# 128x64_ada.net
KiCad netlist of a schematic drawn in EAGLE
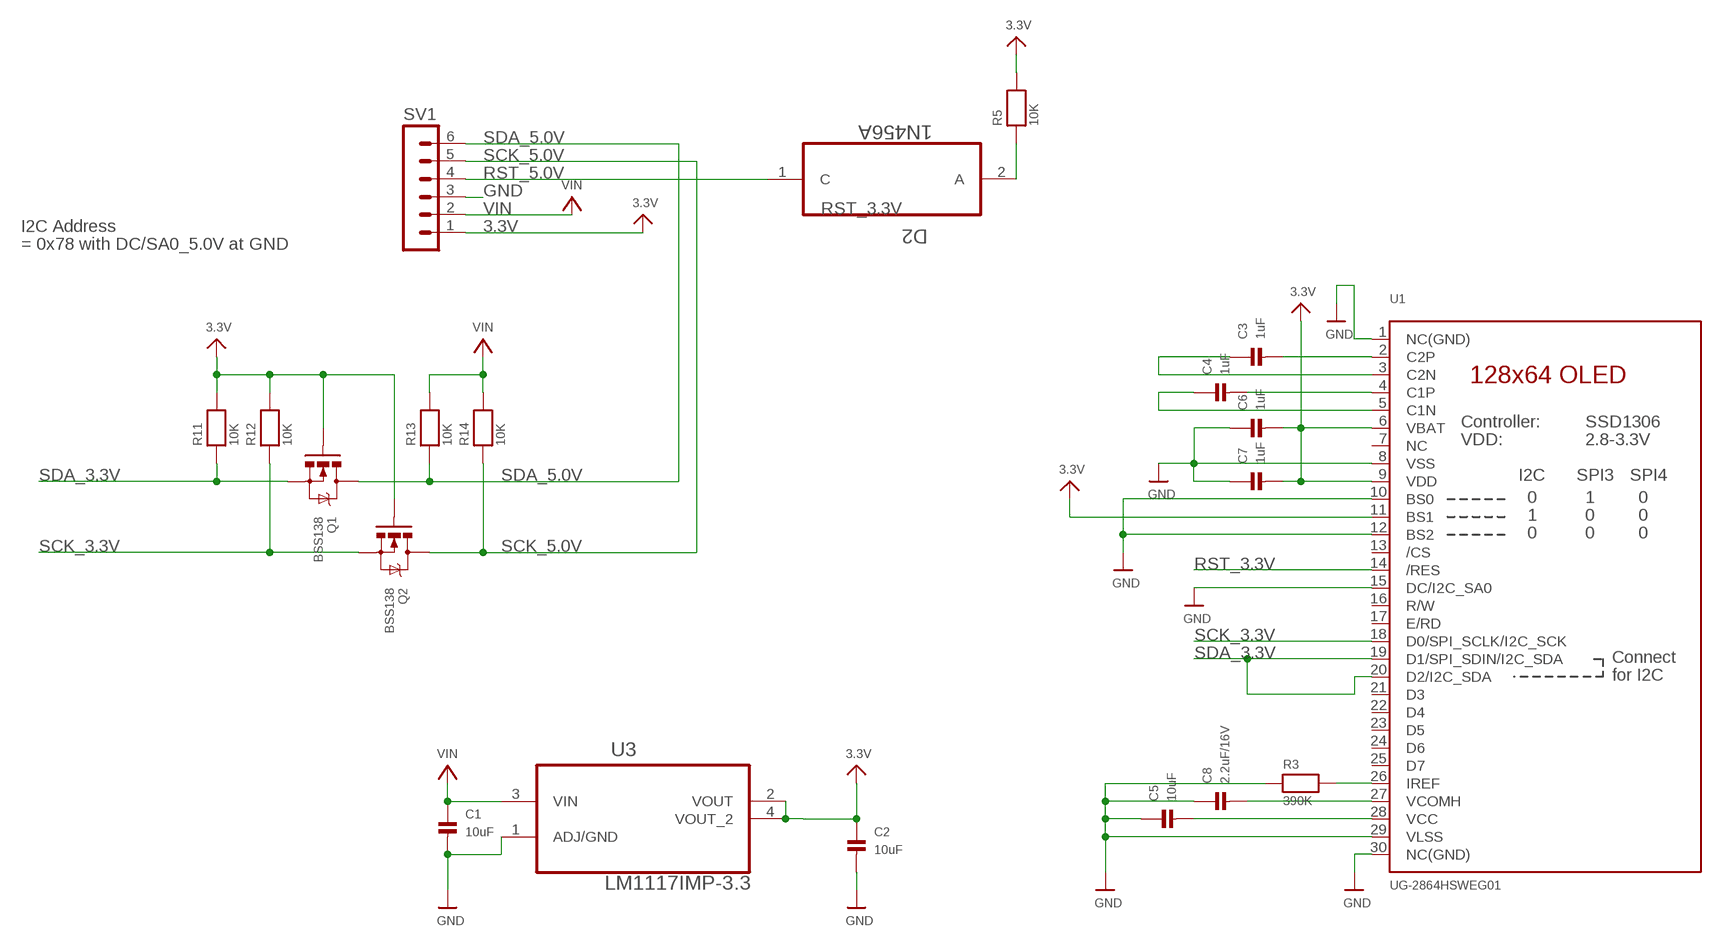
[diagram p0: schematic, sheet 1]

(export (version "E")
  (design (tool "Eeschema 10.0.6"))
  (components
    (comp (ref "C1")
      (value "10uF")
      (footprint "eagle-import:0805")
      (libsource (lib "eagle-import") (part "CAP_CERAMIC0805"))
    )
    (comp (ref "C2")
      (value "10uF")
      (footprint "eagle-import:0805")
      (libsource (lib "eagle-import") (part "CAP_CERAMIC0805"))
    )
    (comp (ref "C3")
      (value "1uF")
      (footprint "eagle-import:0805")
      (libsource (lib "eagle-import") (part "CAP_CERAMIC0805"))
    )
    (comp (ref "C4")
      (value "1uF")
      (footprint "eagle-import:0805")
      (libsource (lib "eagle-import") (part "CAP_CERAMIC0805"))
    )
    (comp (ref "C5")
      (value "10uF")
      (footprint "eagle-import:0805")
      (libsource (lib "eagle-import") (part "CAP_CERAMIC0805"))
    )
    (comp (ref "C6")
      (value "1uF")
      (footprint "eagle-import:0805")
      (libsource (lib "eagle-import") (part "CAP_CERAMIC0805"))
    )
    (comp (ref "C7")
      (value "1uF")
      (footprint "eagle-import:0805")
      (libsource (lib "eagle-import") (part "CAP_CERAMIC0805"))
    )
    (comp (ref "C8")
      (value "2.2uF/16V")
      (footprint "eagle-import:0805")
      (libsource (lib "eagle-import") (part "CAP_CERAMIC0805"))
    )
    (comp (ref "D2")
      (value "1N456A")
      (footprint "eagle-import:DIO_1N456A")
      (libsource (lib "eagle-import") (part "1N456A"))
    )
    (comp (ref "Q1")
      (value "BSS138")
      (footprint "eagle-import:SOT323")
      (libsource (lib "eagle-import") (part "MOSFET-NCHANNEL2N7002PW"))
    )
    (comp (ref "Q2")
      (value "BSS138")
      (footprint "eagle-import:SOT323")
      (libsource (lib "eagle-import") (part "MOSFET-NCHANNEL2N7002PW"))
    )
    (comp (ref "R3")
      (value "390K")
      (footprint "eagle-import:0805")
      (libsource (lib "eagle-import") (part "RESISTOR0805"))
    )
    (comp (ref "R5")
      (value "10K")
      (footprint "eagle-import:0603")
      (libsource (lib "eagle-import") (part "RESISTOR0603"))
    )
    (comp (ref "R11")
      (value "10K")
      (footprint "eagle-import:0603")
      (libsource (lib "eagle-import") (part "RESISTOR0603"))
    )
    (comp (ref "R12")
      (value "10K")
      (footprint "eagle-import:0603")
      (libsource (lib "eagle-import") (part "RESISTOR0603"))
    )
    (comp (ref "R13")
      (value "10K")
      (footprint "eagle-import:0603")
      (libsource (lib "eagle-import") (part "RESISTOR0603"))
    )
    (comp (ref "R14")
      (value "10K")
      (footprint "eagle-import:0603")
      (libsource (lib "eagle-import") (part "RESISTOR0603"))
    )
    (comp (ref "SV1")
      (value "MA06-1")
      (footprint "eagle-import:MA06-1")
      (libsource (lib "eagle-import") (part "MA06-1"))
    )
    (comp (ref "U1")
      (value "UG-2864HSWEG01")
      (footprint "eagle-import:UG-2864HSWEG01_0.96IN_WRAPAROUND")
      (libsource (lib "eagle-import") (part "DISP_OLED_UG-2864HSWEG010.96{dblquote}"))
    )
    (comp (ref "U3")
      (value "LM1117IMP-3.3")
      (footprint "eagle-import:SOT230P696X180-4N")
      (libsource (lib "eagle-import") (part "LM1117IMP-3.3"))
    )
  )
  (nets
    (net (code "1") (name "/RST_3.3V") (class "Default")
      (node (ref "D2") (pin "2") (pinfunction "A_2") (pintype "passive"))
      (node (ref "R5") (pin "1") (pinfunction "1_1") (pintype "passive"))
      (node (ref "U1") (pin "14") (pinfunction "/RES_14") (pintype "input"))
    )
    (net (code "2") (name "/RST_5.0V") (class "Default")
      (node (ref "D2") (pin "1") (pinfunction "C_1") (pintype "passive"))
      (node (ref "SV1") (pin "4") (pinfunction "4_4") (pintype "passive"))
    )
    (net (code "3") (name "/SCK_3.3V") (class "Default")
      (node (ref "Q2") (pin "2") (pinfunction "S_2") (pintype "passive"))
      (node (ref "R12") (pin "1") (pinfunction "1_1") (pintype "passive"))
      (node (ref "U1") (pin "18") (pinfunction "D0/SPI_SCLK/I2C_SCK_18") (pintype "bidirectional"))
    )
    (net (code "4") (name "/SCK_5.0V") (class "Default")
      (node (ref "Q2") (pin "3") (pinfunction "D_3") (pintype "passive"))
      (node (ref "R14") (pin "1") (pinfunction "1_1") (pintype "passive"))
      (node (ref "SV1") (pin "5") (pinfunction "5_5") (pintype "passive"))
    )
    (net (code "5") (name "/SDA_3.3V") (class "Default")
      (node (ref "Q1") (pin "2") (pinfunction "S_2") (pintype "passive"))
      (node (ref "R11") (pin "1") (pinfunction "1_1") (pintype "passive"))
      (node (ref "U1") (pin "19") (pinfunction "D1/SPI_SDIN/I2C_SDA_19") (pintype "bidirectional"))
      (node (ref "U1") (pin "20") (pinfunction "D2/I2C_SDA_20") (pintype "bidirectional"))
    )
    (net (code "6") (name "/SDA_5.0V") (class "Default")
      (node (ref "Q1") (pin "3") (pinfunction "D_3") (pintype "passive"))
      (node (ref "R13") (pin "1") (pinfunction "1_1") (pintype "passive"))
      (node (ref "SV1") (pin "6") (pinfunction "6_6") (pintype "passive"))
    )
    (net (code "7") (name "3.3V") (class "Default")
      (node (ref "C2") (pin "1") (pinfunction "P$1_1") (pintype "passive"))
      (node (ref "C6") (pin "2") (pinfunction "P$2_2") (pintype "passive"))
      (node (ref "C7") (pin "2") (pinfunction "P$2_2") (pintype "passive"))
      (node (ref "Q1") (pin "1") (pinfunction "G_1") (pintype "passive"))
      (node (ref "Q2") (pin "1") (pinfunction "G_1") (pintype "passive"))
      (node (ref "R11") (pin "2") (pinfunction "2_2") (pintype "passive"))
      (node (ref "R12") (pin "2") (pinfunction "2_2") (pintype "passive"))
      (node (ref "R5") (pin "2") (pinfunction "2_2") (pintype "passive"))
      (node (ref "SV1") (pin "1") (pinfunction "1_1") (pintype "passive"))
      (node (ref "U1") (pin "11") (pinfunction "BS1_11") (pintype "input"))
      (node (ref "U1") (pin "6") (pinfunction "VBAT_6") (pintype "input"))
      (node (ref "U1") (pin "9") (pinfunction "VDD_9") (pintype "power_in"))
      (node (ref "U3") (pin "2") (pinfunction "VOUT_2") (pintype "output"))
      (node (ref "U3") (pin "4") (pinfunction "VOUT_2_4") (pintype "output"))
    )
    (net (code "8") (name "GND") (class "Default")
      (node (ref "C1") (pin "2") (pinfunction "P$2_2") (pintype "passive"))
      (node (ref "C2") (pin "2") (pinfunction "P$2_2") (pintype "passive"))
      (node (ref "C5") (pin "1") (pinfunction "P$1_1") (pintype "passive"))
      (node (ref "C6") (pin "1") (pinfunction "P$1_1") (pintype "passive"))
      (node (ref "C7") (pin "1") (pinfunction "P$1_1") (pintype "passive"))
      (node (ref "C8") (pin "1") (pinfunction "P$1_1") (pintype "passive"))
      (node (ref "R3") (pin "1") (pinfunction "1_1") (pintype "passive"))
      (node (ref "SV1") (pin "3") (pinfunction "3_3") (pintype "passive"))
      (node (ref "U1") (pin "1") (pinfunction "NC(GND)_1") (pintype "input"))
      (node (ref "U1") (pin "10") (pinfunction "BS0_10") (pintype "input"))
      (node (ref "U1") (pin "12") (pinfunction "BS2_12") (pintype "input"))
      (node (ref "U1") (pin "15") (pinfunction "DC/I2C_SA0_15") (pintype "input"))
      (node (ref "U1") (pin "29") (pinfunction "VLSS_29") (pintype "power_in"))
      (node (ref "U1") (pin "30") (pinfunction "NC(GND)_30") (pintype "input"))
      (node (ref "U1") (pin "8") (pinfunction "VSS_8") (pintype "power_in"))
      (node (ref "U3") (pin "1") (pinfunction "ADJ/GND_1") (pintype "passive"))
    )
    (net (code "9") (name "Net-(C3-P$1)") (class "Default")
      (node (ref "C3") (pin "1") (pinfunction "P$1_1") (pintype "passive"))
      (node (ref "U1") (pin "3") (pinfunction "C2N_3") (pintype "input"))
    )
    (net (code "10") (name "Net-(C3-P$2)") (class "Default")
      (node (ref "C3") (pin "2") (pinfunction "P$2_2") (pintype "passive"))
      (node (ref "U1") (pin "2") (pinfunction "C2P_2") (pintype "input"))
    )
    (net (code "11") (name "Net-(C4-P$1)") (class "Default")
      (node (ref "C4") (pin "1") (pinfunction "P$1_1") (pintype "passive"))
      (node (ref "U1") (pin "5") (pinfunction "C1N_5") (pintype "input"))
    )
    (net (code "12") (name "Net-(C4-P$2)") (class "Default")
      (node (ref "C4") (pin "2") (pinfunction "P$2_2") (pintype "passive"))
      (node (ref "U1") (pin "4") (pinfunction "C1P_4") (pintype "input"))
    )
    (net (code "13") (name "Net-(C5-P$2)") (class "Default")
      (node (ref "C5") (pin "2") (pinfunction "P$2_2") (pintype "passive"))
      (node (ref "U1") (pin "28") (pinfunction "VCC_28") (pintype "power_in"))
    )
    (net (code "14") (name "Net-(C8-P$2)") (class "Default")
      (node (ref "C8") (pin "2") (pinfunction "P$2_2") (pintype "passive"))
      (node (ref "U1") (pin "27") (pinfunction "VCOMH_27") (pintype "output"))
    )
    (net (code "15") (name "Net-(U1-IREF)") (class "Default")
      (node (ref "R3") (pin "2") (pinfunction "2_2") (pintype "passive"))
      (node (ref "U1") (pin "26") (pinfunction "IREF_26") (pintype "input"))
    )
    (net (code "16") (name "VIN") (class "Default")
      (node (ref "C1") (pin "1") (pinfunction "P$1_1") (pintype "passive"))
      (node (ref "R13") (pin "2") (pinfunction "2_2") (pintype "passive"))
      (node (ref "R14") (pin "2") (pinfunction "2_2") (pintype "passive"))
      (node (ref "SV1") (pin "2") (pinfunction "2_2") (pintype "passive"))
      (node (ref "U3") (pin "3") (pinfunction "VIN_3") (pintype "input"))
    )
    (net (code "17") (name "unconnected-(U1-D3-Pad21)") (class "Default")
      (node (ref "U1") (pin "21") (pinfunction "D3_21") (pintype "bidirectional"))
    )
    (net (code "18") (name "unconnected-(U1-D4-Pad22)") (class "Default")
      (node (ref "U1") (pin "22") (pinfunction "D4_22") (pintype "bidirectional"))
    )
    (net (code "19") (name "unconnected-(U1-D5-Pad23)") (class "Default")
      (node (ref "U1") (pin "23") (pinfunction "D5_23") (pintype "bidirectional"))
    )
    (net (code "20") (name "unconnected-(U1-D6-Pad24)") (class "Default")
      (node (ref "U1") (pin "24") (pinfunction "D6_24") (pintype "bidirectional"))
    )
    (net (code "21") (name "unconnected-(U1-D7-Pad25)") (class "Default")
      (node (ref "U1") (pin "25") (pinfunction "D7_25") (pintype "bidirectional"))
    )
    (net (code "22") (name "unconnected-(U1-E{slash}RD-Pad17)") (class "Default")
      (node (ref "U1") (pin "17") (pinfunction "E/RD_17") (pintype "input"))
    )
    (net (code "23") (name "unconnected-(U1-NC-Pad7)") (class "Default")
      (node (ref "U1") (pin "7") (pinfunction "NC_7") (pintype "no_connect"))
    )
    (net (code "24") (name "unconnected-(U1-R{slash}W-Pad16)") (class "Default")
      (node (ref "U1") (pin "16") (pinfunction "R/W_16") (pintype "input"))
    )
    (net (code "25") (name "unconnected-(U1-{slash}CS-Pad13)") (class "Default")
      (node (ref "U1") (pin "13") (pinfunction "/CS_13") (pintype "input"))
    )
  )
)
